# Intan_Headstage.net
KiCad netlist of a schematic drawn in EAGLE
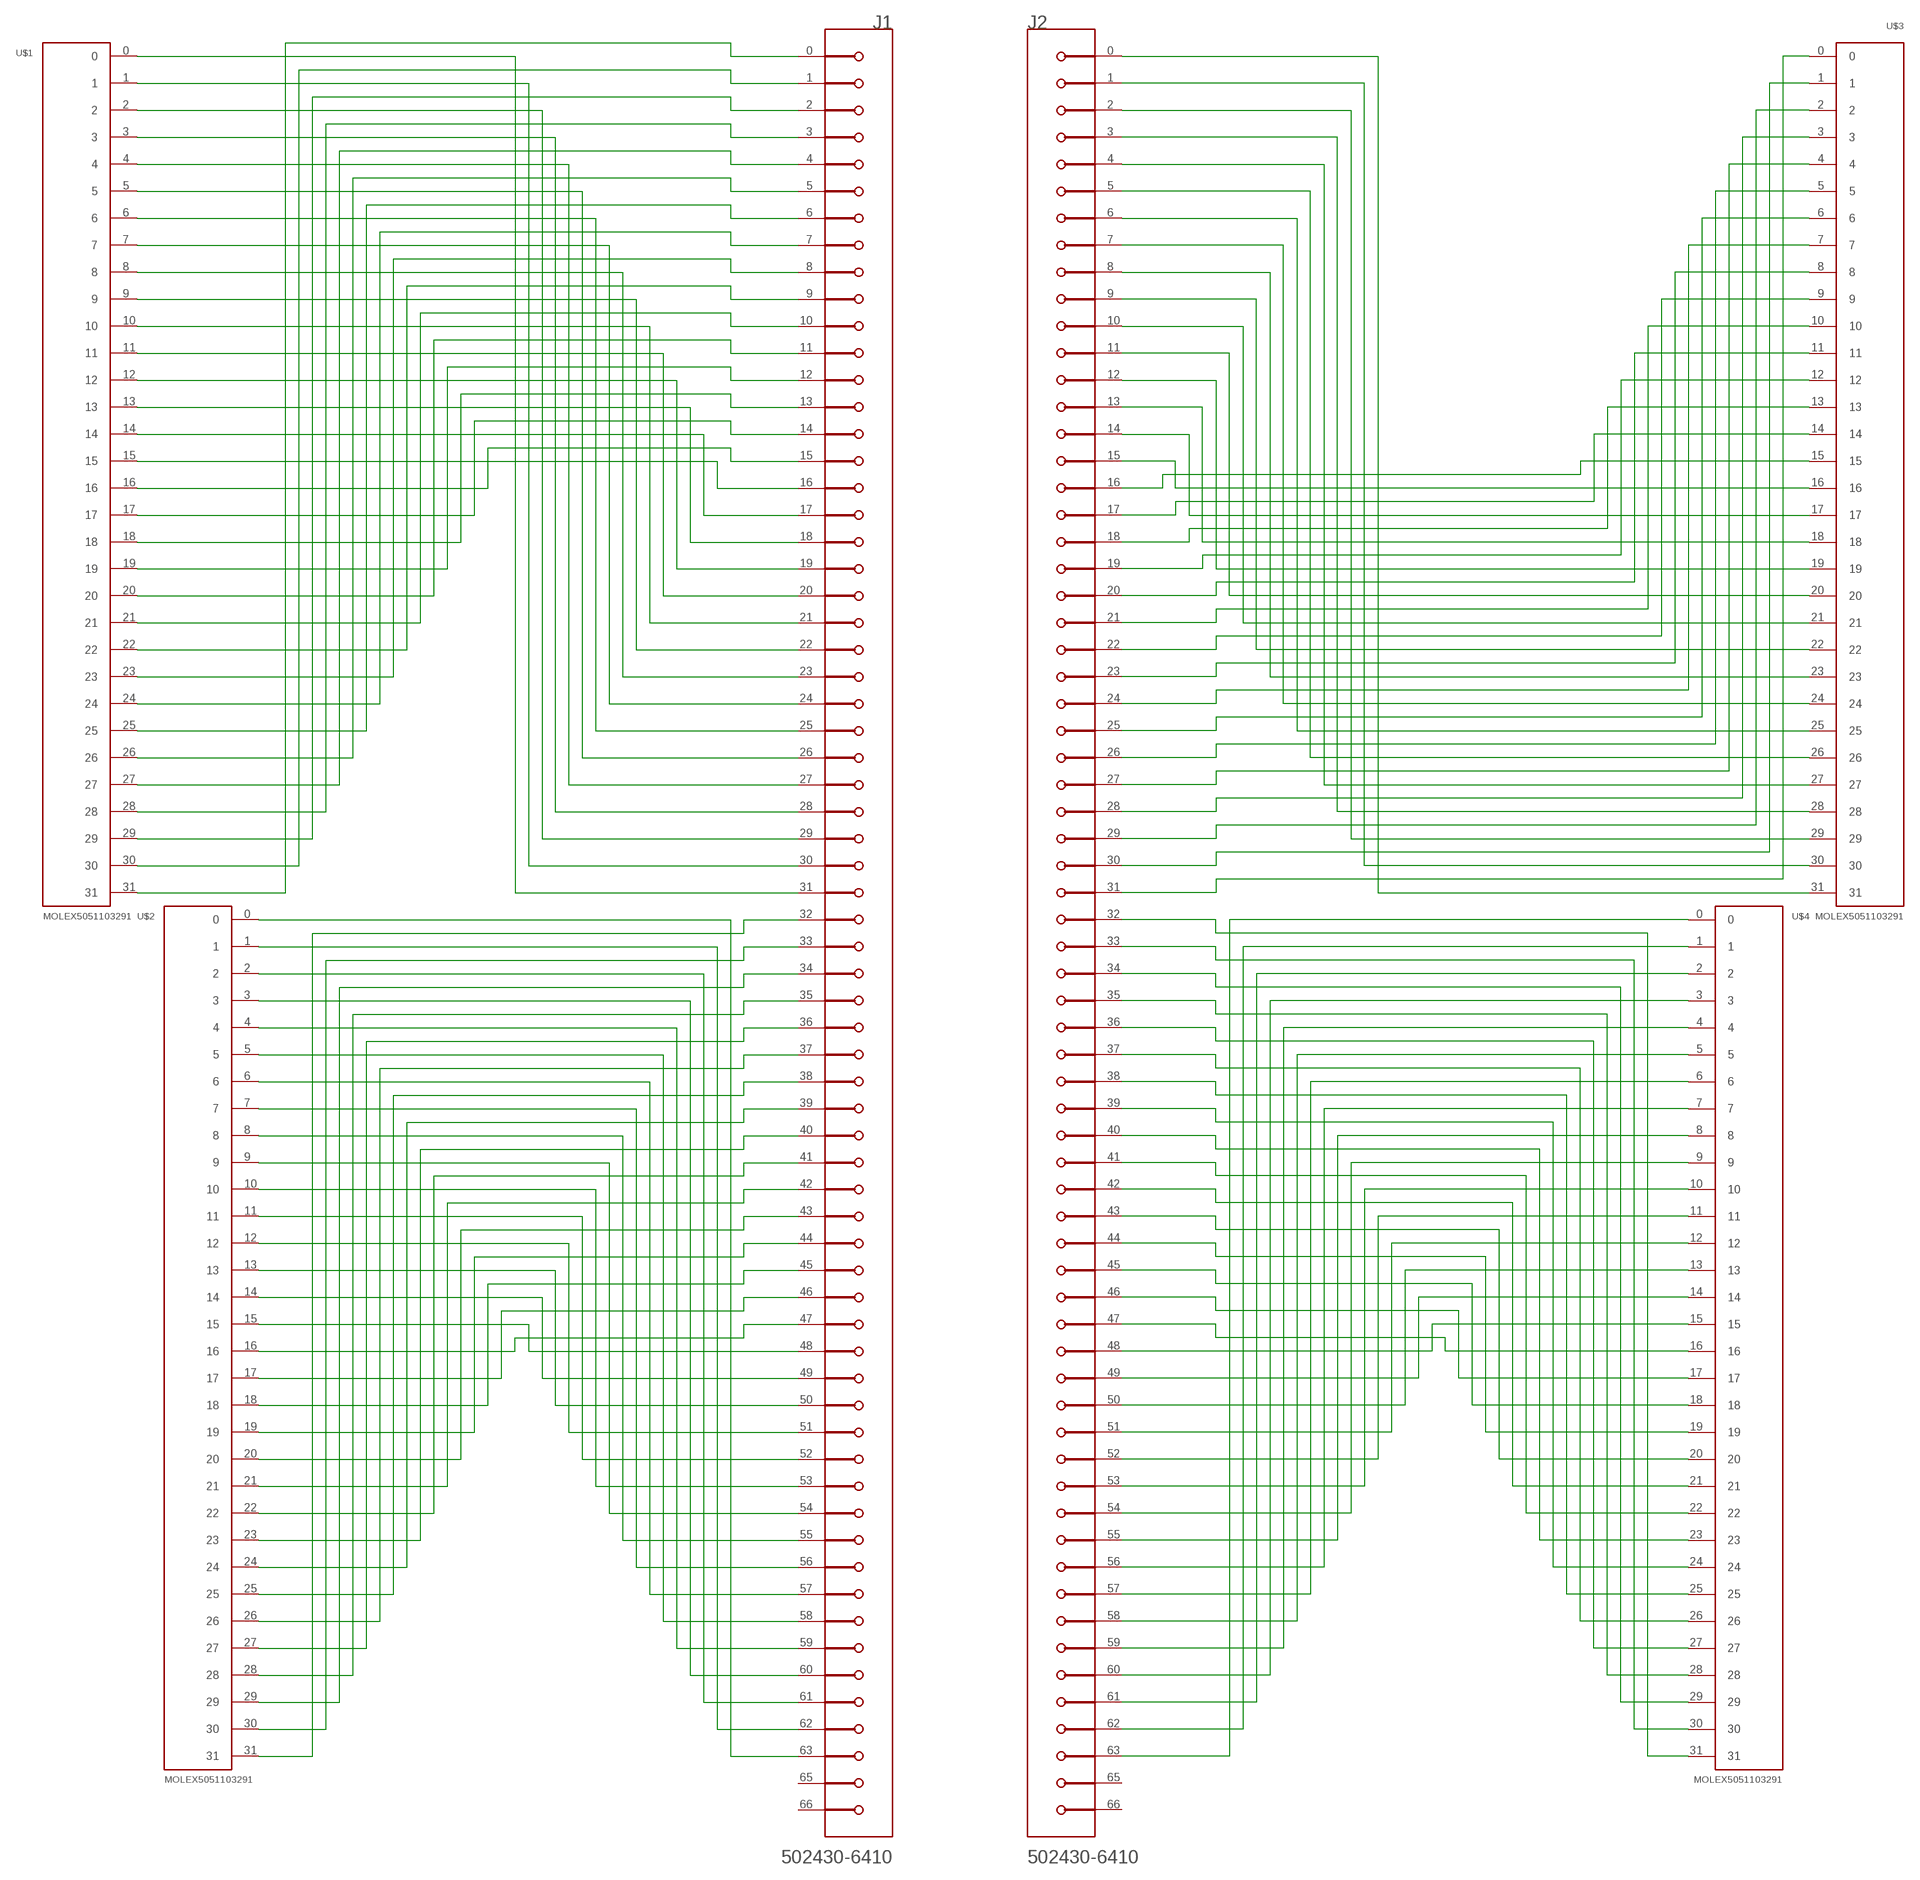
[diagram p0: schematic, sheet 1]

(export (version "E")
  (design (tool "Eeschema 10.0.6"))
  (components
    (comp (ref "J1")
      (value "MOLEX_502430-6410MOLEX_502430-6410_0_0")
      (footprint "eagle-import:MOLEX_502430-6410_0")
      (fields
        (field (name "DIGIKEY_PART_NUMBER") "WM24084TR-ND")
        (field (name "MF") "Molex")
        (field (name "MOUSER_PART_NUMBER") "538-502430-6410")
      )
      (libsource (lib "eagle-import") (part "MOLEX_502430-6410MOLEX_502430-6410_0_0"))
    )
    (comp (ref "J2")
      (value "MOLEX_502430-6410MOLEX_502430-6410_0_0")
      (footprint "eagle-import:MOLEX_502430-6410_0")
      (fields
        (field (name "DIGIKEY_PART_NUMBER") "WM24084TR-ND")
        (field (name "MF") "Molex")
        (field (name "MOUSER_PART_NUMBER") "538-502430-6410")
      )
      (libsource (lib "eagle-import") (part "MOLEX_502430-6410MOLEX_502430-6410_0_0"))
    )
    (comp (ref "U$1")
      (value "MOLEX5051103291")
      (footprint "eagle-import:MOLEX5051103291")
      (libsource (lib "eagle-import") (part "MOLEX5051103291"))
    )
    (comp (ref "U$2")
      (value "MOLEX5051103291")
      (footprint "eagle-import:MOLEX5051103291")
      (libsource (lib "eagle-import") (part "MOLEX5051103291"))
    )
    (comp (ref "U$3")
      (value "MOLEX5051103291")
      (footprint "eagle-import:MOLEX5051103291")
      (libsource (lib "eagle-import") (part "MOLEX5051103291"))
    )
    (comp (ref "U$4")
      (value "MOLEX5051103291")
      (footprint "eagle-import:MOLEX5051103291")
      (libsource (lib "eagle-import") (part "MOLEX5051103291"))
    )
  )
  (nets
    (net (code "1") (name "Net-(J1-1)") (class "Default")
      (node (ref "J1") (pin "0") (pinfunction "1_0") (pintype "bidirectional"))
      (node (ref "U$1") (pin "31") (pinfunction "31_31") (pintype "bidirectional"))
    )
    (net (code "2") (name "Net-(J1-2)") (class "Default")
      (node (ref "J1") (pin "1") (pinfunction "2_1") (pintype "bidirectional"))
      (node (ref "U$1") (pin "30") (pinfunction "30_30") (pintype "bidirectional"))
    )
    (net (code "3") (name "Net-(J1-3)") (class "Default")
      (node (ref "J1") (pin "2") (pinfunction "3_2") (pintype "bidirectional"))
      (node (ref "U$1") (pin "29") (pinfunction "29_29") (pintype "bidirectional"))
    )
    (net (code "4") (name "Net-(J1-4)") (class "Default")
      (node (ref "J1") (pin "3") (pinfunction "4_3") (pintype "bidirectional"))
      (node (ref "U$1") (pin "28") (pinfunction "28_28") (pintype "bidirectional"))
    )
    (net (code "5") (name "Net-(J1-5)") (class "Default")
      (node (ref "J1") (pin "4") (pinfunction "5_4") (pintype "bidirectional"))
      (node (ref "U$1") (pin "27") (pinfunction "27_27") (pintype "bidirectional"))
    )
    (net (code "6") (name "Net-(J1-6)") (class "Default")
      (node (ref "J1") (pin "5") (pinfunction "6_5") (pintype "bidirectional"))
      (node (ref "U$1") (pin "26") (pinfunction "26_26") (pintype "bidirectional"))
    )
    (net (code "7") (name "Net-(J1-7)") (class "Default")
      (node (ref "J1") (pin "6") (pinfunction "7_6") (pintype "bidirectional"))
      (node (ref "U$1") (pin "25") (pinfunction "25_25") (pintype "bidirectional"))
    )
    (net (code "8") (name "Net-(J1-8)") (class "Default")
      (node (ref "J1") (pin "7") (pinfunction "8_7") (pintype "bidirectional"))
      (node (ref "U$1") (pin "24") (pinfunction "24_24") (pintype "bidirectional"))
    )
    (net (code "9") (name "Net-(J1-9)") (class "Default")
      (node (ref "J1") (pin "8") (pinfunction "9_8") (pintype "bidirectional"))
      (node (ref "U$1") (pin "23") (pinfunction "23_23") (pintype "bidirectional"))
    )
    (net (code "10") (name "Net-(J1-10)") (class "Default")
      (node (ref "J1") (pin "9") (pinfunction "10_9") (pintype "bidirectional"))
      (node (ref "U$1") (pin "22") (pinfunction "22_22") (pintype "bidirectional"))
    )
    (net (code "11") (name "Net-(J1-11)") (class "Default")
      (node (ref "J1") (pin "10") (pinfunction "11_10") (pintype "bidirectional"))
      (node (ref "U$1") (pin "21") (pinfunction "21_21") (pintype "bidirectional"))
    )
    (net (code "12") (name "Net-(J1-12)") (class "Default")
      (node (ref "J1") (pin "11") (pinfunction "12_11") (pintype "bidirectional"))
      (node (ref "U$1") (pin "20") (pinfunction "20_20") (pintype "bidirectional"))
    )
    (net (code "13") (name "Net-(J1-13)") (class "Default")
      (node (ref "J1") (pin "12") (pinfunction "13_12") (pintype "bidirectional"))
      (node (ref "U$1") (pin "19") (pinfunction "19_19") (pintype "bidirectional"))
    )
    (net (code "14") (name "Net-(J1-14)") (class "Default")
      (node (ref "J1") (pin "13") (pinfunction "14_13") (pintype "bidirectional"))
      (node (ref "U$1") (pin "18") (pinfunction "18_18") (pintype "bidirectional"))
    )
    (net (code "15") (name "Net-(J1-15)") (class "Default")
      (node (ref "J1") (pin "14") (pinfunction "15_14") (pintype "bidirectional"))
      (node (ref "U$1") (pin "17") (pinfunction "17_17") (pintype "bidirectional"))
    )
    (net (code "16") (name "Net-(J1-16)") (class "Default")
      (node (ref "J1") (pin "15") (pinfunction "16_15") (pintype "bidirectional"))
      (node (ref "U$1") (pin "16") (pinfunction "16_16") (pintype "bidirectional"))
    )
    (net (code "17") (name "Net-(J1-17)") (class "Default")
      (node (ref "J1") (pin "16") (pinfunction "17_16") (pintype "bidirectional"))
      (node (ref "U$1") (pin "15") (pinfunction "15_15") (pintype "bidirectional"))
    )
    (net (code "18") (name "Net-(J1-18)") (class "Default")
      (node (ref "J1") (pin "17") (pinfunction "18_17") (pintype "bidirectional"))
      (node (ref "U$1") (pin "14") (pinfunction "14_14") (pintype "bidirectional"))
    )
    (net (code "19") (name "Net-(J1-19)") (class "Default")
      (node (ref "J1") (pin "18") (pinfunction "19_18") (pintype "bidirectional"))
      (node (ref "U$1") (pin "13") (pinfunction "13_13") (pintype "bidirectional"))
    )
    (net (code "20") (name "Net-(J1-20)") (class "Default")
      (node (ref "J1") (pin "19") (pinfunction "20_19") (pintype "bidirectional"))
      (node (ref "U$1") (pin "12") (pinfunction "12_12") (pintype "bidirectional"))
    )
    (net (code "21") (name "Net-(J1-21)") (class "Default")
      (node (ref "J1") (pin "20") (pinfunction "21_20") (pintype "bidirectional"))
      (node (ref "U$1") (pin "11") (pinfunction "11_11") (pintype "bidirectional"))
    )
    (net (code "22") (name "Net-(J1-22)") (class "Default")
      (node (ref "J1") (pin "21") (pinfunction "22_21") (pintype "bidirectional"))
      (node (ref "U$1") (pin "10") (pinfunction "10_10") (pintype "bidirectional"))
    )
    (net (code "23") (name "Net-(J1-23)") (class "Default")
      (node (ref "J1") (pin "22") (pinfunction "23_22") (pintype "bidirectional"))
      (node (ref "U$1") (pin "9") (pinfunction "9_9") (pintype "bidirectional"))
    )
    (net (code "24") (name "Net-(J1-24)") (class "Default")
      (node (ref "J1") (pin "23") (pinfunction "24_23") (pintype "bidirectional"))
      (node (ref "U$1") (pin "8") (pinfunction "8_8") (pintype "bidirectional"))
    )
    (net (code "25") (name "Net-(J1-25)") (class "Default")
      (node (ref "J1") (pin "24") (pinfunction "25_24") (pintype "bidirectional"))
      (node (ref "U$1") (pin "7") (pinfunction "7_7") (pintype "bidirectional"))
    )
    (net (code "26") (name "Net-(J1-26)") (class "Default")
      (node (ref "J1") (pin "25") (pinfunction "26_25") (pintype "bidirectional"))
      (node (ref "U$1") (pin "6") (pinfunction "6_6") (pintype "bidirectional"))
    )
    (net (code "27") (name "Net-(J1-27)") (class "Default")
      (node (ref "J1") (pin "26") (pinfunction "27_26") (pintype "bidirectional"))
      (node (ref "U$1") (pin "5") (pinfunction "5_5") (pintype "bidirectional"))
    )
    (net (code "28") (name "Net-(J1-28)") (class "Default")
      (node (ref "J1") (pin "27") (pinfunction "28_27") (pintype "bidirectional"))
      (node (ref "U$1") (pin "4") (pinfunction "4_4") (pintype "bidirectional"))
    )
    (net (code "29") (name "Net-(J1-29)") (class "Default")
      (node (ref "J1") (pin "28") (pinfunction "29_28") (pintype "bidirectional"))
      (node (ref "U$1") (pin "3") (pinfunction "3_3") (pintype "bidirectional"))
    )
    (net (code "30") (name "Net-(J1-30)") (class "Default")
      (node (ref "J1") (pin "29") (pinfunction "30_29") (pintype "bidirectional"))
      (node (ref "U$1") (pin "2") (pinfunction "2_2") (pintype "bidirectional"))
    )
    (net (code "31") (name "Net-(J1-31)") (class "Default")
      (node (ref "J1") (pin "30") (pinfunction "31_30") (pintype "bidirectional"))
      (node (ref "U$1") (pin "1") (pinfunction "1_1") (pintype "bidirectional"))
    )
    (net (code "32") (name "Net-(J1-32)") (class "Default")
      (node (ref "J1") (pin "31") (pinfunction "32_31") (pintype "bidirectional"))
      (node (ref "U$1") (pin "0") (pinfunction "0_0") (pintype "bidirectional"))
    )
    (net (code "33") (name "Net-(J1-33)") (class "Default")
      (node (ref "J1") (pin "32") (pinfunction "33_32") (pintype "bidirectional"))
      (node (ref "U$2") (pin "31") (pinfunction "31_31") (pintype "bidirectional"))
    )
    (net (code "34") (name "Net-(J1-34)") (class "Default")
      (node (ref "J1") (pin "33") (pinfunction "34_33") (pintype "bidirectional"))
      (node (ref "U$2") (pin "30") (pinfunction "30_30") (pintype "bidirectional"))
    )
    (net (code "35") (name "Net-(J1-35)") (class "Default")
      (node (ref "J1") (pin "34") (pinfunction "35_34") (pintype "bidirectional"))
      (node (ref "U$2") (pin "29") (pinfunction "29_29") (pintype "bidirectional"))
    )
    (net (code "36") (name "Net-(J1-36)") (class "Default")
      (node (ref "J1") (pin "35") (pinfunction "36_35") (pintype "bidirectional"))
      (node (ref "U$2") (pin "28") (pinfunction "28_28") (pintype "bidirectional"))
    )
    (net (code "37") (name "Net-(J1-37)") (class "Default")
      (node (ref "J1") (pin "36") (pinfunction "37_36") (pintype "bidirectional"))
      (node (ref "U$2") (pin "27") (pinfunction "27_27") (pintype "bidirectional"))
    )
    (net (code "38") (name "Net-(J1-38)") (class "Default")
      (node (ref "J1") (pin "37") (pinfunction "38_37") (pintype "bidirectional"))
      (node (ref "U$2") (pin "26") (pinfunction "26_26") (pintype "bidirectional"))
    )
    (net (code "39") (name "Net-(J1-39)") (class "Default")
      (node (ref "J1") (pin "38") (pinfunction "39_38") (pintype "bidirectional"))
      (node (ref "U$2") (pin "25") (pinfunction "25_25") (pintype "bidirectional"))
    )
    (net (code "40") (name "Net-(J1-40)") (class "Default")
      (node (ref "J1") (pin "39") (pinfunction "40_39") (pintype "bidirectional"))
      (node (ref "U$2") (pin "24") (pinfunction "24_24") (pintype "bidirectional"))
    )
    (net (code "41") (name "Net-(J1-41)") (class "Default")
      (node (ref "J1") (pin "40") (pinfunction "41_40") (pintype "bidirectional"))
      (node (ref "U$2") (pin "23") (pinfunction "23_23") (pintype "bidirectional"))
    )
    (net (code "42") (name "Net-(J1-42)") (class "Default")
      (node (ref "J1") (pin "41") (pinfunction "42_41") (pintype "bidirectional"))
      (node (ref "U$2") (pin "22") (pinfunction "22_22") (pintype "bidirectional"))
    )
    (net (code "43") (name "Net-(J1-43)") (class "Default")
      (node (ref "J1") (pin "42") (pinfunction "43_42") (pintype "bidirectional"))
      (node (ref "U$2") (pin "21") (pinfunction "21_21") (pintype "bidirectional"))
    )
    (net (code "44") (name "Net-(J1-44)") (class "Default")
      (node (ref "J1") (pin "43") (pinfunction "44_43") (pintype "bidirectional"))
      (node (ref "U$2") (pin "20") (pinfunction "20_20") (pintype "bidirectional"))
    )
    (net (code "45") (name "Net-(J1-45)") (class "Default")
      (node (ref "J1") (pin "44") (pinfunction "45_44") (pintype "bidirectional"))
      (node (ref "U$2") (pin "19") (pinfunction "19_19") (pintype "bidirectional"))
    )
    (net (code "46") (name "Net-(J1-46)") (class "Default")
      (node (ref "J1") (pin "45") (pinfunction "46_45") (pintype "bidirectional"))
      (node (ref "U$2") (pin "18") (pinfunction "18_18") (pintype "bidirectional"))
    )
    (net (code "47") (name "Net-(J1-47)") (class "Default")
      (node (ref "J1") (pin "46") (pinfunction "47_46") (pintype "bidirectional"))
      (node (ref "U$2") (pin "17") (pinfunction "17_17") (pintype "bidirectional"))
    )
    (net (code "48") (name "Net-(J1-48)") (class "Default")
      (node (ref "J1") (pin "47") (pinfunction "48_47") (pintype "bidirectional"))
      (node (ref "U$2") (pin "16") (pinfunction "16_16") (pintype "bidirectional"))
    )
    (net (code "49") (name "Net-(J1-49)") (class "Default")
      (node (ref "J1") (pin "48") (pinfunction "49_48") (pintype "bidirectional"))
      (node (ref "U$2") (pin "15") (pinfunction "15_15") (pintype "bidirectional"))
    )
    (net (code "50") (name "Net-(J1-50)") (class "Default")
      (node (ref "J1") (pin "49") (pinfunction "50_49") (pintype "bidirectional"))
      (node (ref "U$2") (pin "14") (pinfunction "14_14") (pintype "bidirectional"))
    )
    (net (code "51") (name "Net-(J1-51)") (class "Default")
      (node (ref "J1") (pin "50") (pinfunction "51_50") (pintype "bidirectional"))
      (node (ref "U$2") (pin "13") (pinfunction "13_13") (pintype "bidirectional"))
    )
    (net (code "52") (name "Net-(J1-52)") (class "Default")
      (node (ref "J1") (pin "51") (pinfunction "52_51") (pintype "bidirectional"))
      (node (ref "U$2") (pin "12") (pinfunction "12_12") (pintype "bidirectional"))
    )
    (net (code "53") (name "Net-(J1-53)") (class "Default")
      (node (ref "J1") (pin "52") (pinfunction "53_52") (pintype "bidirectional"))
      (node (ref "U$2") (pin "11") (pinfunction "11_11") (pintype "bidirectional"))
    )
    (net (code "54") (name "Net-(J1-54)") (class "Default")
      (node (ref "J1") (pin "53") (pinfunction "54_53") (pintype "bidirectional"))
      (node (ref "U$2") (pin "10") (pinfunction "10_10") (pintype "bidirectional"))
    )
    (net (code "55") (name "Net-(J1-55)") (class "Default")
      (node (ref "J1") (pin "54") (pinfunction "55_54") (pintype "bidirectional"))
      (node (ref "U$2") (pin "9") (pinfunction "9_9") (pintype "bidirectional"))
    )
    (net (code "56") (name "Net-(J1-56)") (class "Default")
      (node (ref "J1") (pin "55") (pinfunction "56_55") (pintype "bidirectional"))
      (node (ref "U$2") (pin "8") (pinfunction "8_8") (pintype "bidirectional"))
    )
    (net (code "57") (name "Net-(J1-57)") (class "Default")
      (node (ref "J1") (pin "56") (pinfunction "57_56") (pintype "bidirectional"))
      (node (ref "U$2") (pin "7") (pinfunction "7_7") (pintype "bidirectional"))
    )
    (net (code "58") (name "Net-(J1-58)") (class "Default")
      (node (ref "J1") (pin "57") (pinfunction "58_57") (pintype "bidirectional"))
      (node (ref "U$2") (pin "6") (pinfunction "6_6") (pintype "bidirectional"))
    )
    (net (code "59") (name "Net-(J1-59)") (class "Default")
      (node (ref "J1") (pin "58") (pinfunction "59_58") (pintype "bidirectional"))
      (node (ref "U$2") (pin "5") (pinfunction "5_5") (pintype "bidirectional"))
    )
    (net (code "60") (name "Net-(J1-60)") (class "Default")
      (node (ref "J1") (pin "59") (pinfunction "60_59") (pintype "bidirectional"))
      (node (ref "U$2") (pin "4") (pinfunction "4_4") (pintype "bidirectional"))
    )
    (net (code "61") (name "Net-(J1-61)") (class "Default")
      (node (ref "J1") (pin "60") (pinfunction "61_60") (pintype "bidirectional"))
      (node (ref "U$2") (pin "3") (pinfunction "3_3") (pintype "bidirectional"))
    )
    (net (code "62") (name "Net-(J1-62)") (class "Default")
      (node (ref "J1") (pin "61") (pinfunction "62_61") (pintype "bidirectional"))
      (node (ref "U$2") (pin "2") (pinfunction "2_2") (pintype "bidirectional"))
    )
    (net (code "63") (name "Net-(J1-63)") (class "Default")
      (node (ref "J1") (pin "62") (pinfunction "63_62") (pintype "bidirectional"))
      (node (ref "U$2") (pin "1") (pinfunction "1_1") (pintype "bidirectional"))
    )
    (net (code "64") (name "Net-(J1-64)") (class "Default")
      (node (ref "J1") (pin "63") (pinfunction "64_63") (pintype "bidirectional"))
      (node (ref "U$2") (pin "0") (pinfunction "0_0") (pintype "bidirectional"))
    )
    (net (code "65") (name "Net-(J2-1)") (class "Default")
      (node (ref "J2") (pin "0") (pinfunction "1_0") (pintype "bidirectional"))
      (node (ref "U$3") (pin "31") (pinfunction "31_31") (pintype "bidirectional"))
    )
    (net (code "66") (name "Net-(J2-2)") (class "Default")
      (node (ref "J2") (pin "1") (pinfunction "2_1") (pintype "bidirectional"))
      (node (ref "U$3") (pin "30") (pinfunction "30_30") (pintype "bidirectional"))
    )
    (net (code "67") (name "Net-(J2-3)") (class "Default")
      (node (ref "J2") (pin "2") (pinfunction "3_2") (pintype "bidirectional"))
      (node (ref "U$3") (pin "29") (pinfunction "29_29") (pintype "bidirectional"))
    )
    (net (code "68") (name "Net-(J2-4)") (class "Default")
      (node (ref "J2") (pin "3") (pinfunction "4_3") (pintype "bidirectional"))
      (node (ref "U$3") (pin "28") (pinfunction "28_28") (pintype "bidirectional"))
    )
    (net (code "69") (name "Net-(J2-5)") (class "Default")
      (node (ref "J2") (pin "4") (pinfunction "5_4") (pintype "bidirectional"))
      (node (ref "U$3") (pin "27") (pinfunction "27_27") (pintype "bidirectional"))
    )
    (net (code "70") (name "Net-(J2-6)") (class "Default")
      (node (ref "J2") (pin "5") (pinfunction "6_5") (pintype "bidirectional"))
      (node (ref "U$3") (pin "26") (pinfunction "26_26") (pintype "bidirectional"))
    )
    (net (code "71") (name "Net-(J2-7)") (class "Default")
      (node (ref "J2") (pin "6") (pinfunction "7_6") (pintype "bidirectional"))
      (node (ref "U$3") (pin "25") (pinfunction "25_25") (pintype "bidirectional"))
    )
    (net (code "72") (name "Net-(J2-8)") (class "Default")
      (node (ref "J2") (pin "7") (pinfunction "8_7") (pintype "bidirectional"))
      (node (ref "U$3") (pin "24") (pinfunction "24_24") (pintype "bidirectional"))
    )
    (net (code "73") (name "Net-(J2-9)") (class "Default")
      (node (ref "J2") (pin "8") (pinfunction "9_8") (pintype "bidirectional"))
      (node (ref "U$3") (pin "23") (pinfunction "23_23") (pintype "bidirectional"))
    )
    (net (code "74") (name "Net-(J2-10)") (class "Default")
      (node (ref "J2") (pin "9") (pinfunction "10_9") (pintype "bidirectional"))
      (node (ref "U$3") (pin "22") (pinfunction "22_22") (pintype "bidirectional"))
    )
    (net (code "75") (name "Net-(J2-11)") (class "Default")
      (node (ref "J2") (pin "10") (pinfunction "11_10") (pintype "bidirectional"))
      (node (ref "U$3") (pin "21") (pinfunction "21_21") (pintype "bidirectional"))
    )
    (net (code "76") (name "Net-(J2-12)") (class "Default")
      (node (ref "J2") (pin "11") (pinfunction "12_11") (pintype "bidirectional"))
      (node (ref "U$3") (pin "20") (pinfunction "20_20") (pintype "bidirectional"))
    )
    (net (code "77") (name "Net-(J2-13)") (class "Default")
      (node (ref "J2") (pin "12") (pinfunction "13_12") (pintype "bidirectional"))
      (node (ref "U$3") (pin "19") (pinfunction "19_19") (pintype "bidirectional"))
    )
    (net (code "78") (name "Net-(J2-14)") (class "Default")
      (node (ref "J2") (pin "13") (pinfunction "14_13") (pintype "bidirectional"))
      (node (ref "U$3") (pin "18") (pinfunction "18_18") (pintype "bidirectional"))
    )
    (net (code "79") (name "Net-(J2-15)") (class "Default")
      (node (ref "J2") (pin "14") (pinfunction "15_14") (pintype "bidirectional"))
      (node (ref "U$3") (pin "17") (pinfunction "17_17") (pintype "bidirectional"))
    )
    (net (code "80") (name "Net-(J2-16)") (class "Default")
      (node (ref "J2") (pin "15") (pinfunction "16_15") (pintype "bidirectional"))
      (node (ref "U$3") (pin "16") (pinfunction "16_16") (pintype "bidirectional"))
    )
    (net (code "81") (name "Net-(J2-17)") (class "Default")
      (node (ref "J2") (pin "16") (pinfunction "17_16") (pintype "bidirectional"))
      (node (ref "U$3") (pin "15") (pinfunction "15_15") (pintype "bidirectional"))
    )
    (net (code "82") (name "Net-(J2-18)") (class "Default")
      (node (ref "J2") (pin "17") (pinfunction "18_17") (pintype "bidirectional"))
      (node (ref "U$3") (pin "14") (pinfunction "14_14") (pintype "bidirectional"))
    )
    (net (code "83") (name "Net-(J2-19)") (class "Default")
      (node (ref "J2") (pin "18") (pinfunction "19_18") (pintype "bidirectional"))
      (node (ref "U$3") (pin "13") (pinfunction "13_13") (pintype "bidirectional"))
    )
    (net (code "84") (name "Net-(J2-20)") (class "Default")
      (node (ref "J2") (pin "19") (pinfunction "20_19") (pintype "bidirectional"))
      (node (ref "U$3") (pin "12") (pinfunction "12_12") (pintype "bidirectional"))
    )
    (net (code "85") (name "Net-(J2-21)") (class "Default")
      (node (ref "J2") (pin "20") (pinfunction "21_20") (pintype "bidirectional"))
      (node (ref "U$3") (pin "11") (pinfunction "11_11") (pintype "bidirectional"))
    )
    (net (code "86") (name "Net-(J2-22)") (class "Default")
      (node (ref "J2") (pin "21") (pinfunction "22_21") (pintype "bidirectional"))
      (node (ref "U$3") (pin "10") (pinfunction "10_10") (pintype "bidirectional"))
    )
    (net (code "87") (name "Net-(J2-23)") (class "Default")
      (node (ref "J2") (pin "22") (pinfunction "23_22") (pintype "bidirectional"))
      (node (ref "U$3") (pin "9") (pinfunction "9_9") (pintype "bidirectional"))
    )
    (net (code "88") (name "Net-(J2-24)") (class "Default")
      (node (ref "J2") (pin "23") (pinfunction "24_23") (pintype "bidirectional"))
      (node (ref "U$3") (pin "8") (pinfunction "8_8") (pintype "bidirectional"))
    )
    (net (code "89") (name "Net-(J2-25)") (class "Default")
      (node (ref "J2") (pin "24") (pinfunction "25_24") (pintype "bidirectional"))
      (node (ref "U$3") (pin "7") (pinfunction "7_7") (pintype "bidirectional"))
    )
    (net (code "90") (name "Net-(J2-26)") (class "Default")
      (node (ref "J2") (pin "25") (pinfunction "26_25") (pintype "bidirectional"))
      (node (ref "U$3") (pin "6") (pinfunction "6_6") (pintype "bidirectional"))
    )
    (net (code "91") (name "Net-(J2-27)") (class "Default")
      (node (ref "J2") (pin "26") (pinfunction "27_26") (pintype "bidirectional"))
      (node (ref "U$3") (pin "5") (pinfunction "5_5") (pintype "bidirectional"))
    )
    (net (code "92") (name "Net-(J2-28)") (class "Default")
      (node (ref "J2") (pin "27") (pinfunction "28_27") (pintype "bidirectional"))
      (node (ref "U$3") (pin "4") (pinfunction "4_4") (pintype "bidirectional"))
    )
    (net (code "93") (name "Net-(J2-29)") (class "Default")
      (node (ref "J2") (pin "28") (pinfunction "29_28") (pintype "bidirectional"))
      (node (ref "U$3") (pin "3") (pinfunction "3_3") (pintype "bidirectional"))
    )
    (net (code "94") (name "Net-(J2-30)") (class "Default")
      (node (ref "J2") (pin "29") (pinfunction "30_29") (pintype "bidirectional"))
      (node (ref "U$3") (pin "2") (pinfunction "2_2") (pintype "bidirectional"))
    )
    (net (code "95") (name "Net-(J2-31)") (class "Default")
      (node (ref "J2") (pin "30") (pinfunction "31_30") (pintype "bidirectional"))
      (node (ref "U$3") (pin "1") (pinfunction "1_1") (pintype "bidirectional"))
    )
    (net (code "96") (name "Net-(J2-32)") (class "Default")
      (node (ref "J2") (pin "31") (pinfunction "32_31") (pintype "bidirectional"))
      (node (ref "U$3") (pin "0") (pinfunction "0_0") (pintype "bidirectional"))
    )
    (net (code "97") (name "Net-(J2-33)") (class "Default")
      (node (ref "J2") (pin "32") (pinfunction "33_32") (pintype "bidirectional"))
      (node (ref "U$4") (pin "31") (pinfunction "31_31") (pintype "bidirectional"))
    )
    (net (code "98") (name "Net-(J2-34)") (class "Default")
      (node (ref "J2") (pin "33") (pinfunction "34_33") (pintype "bidirectional"))
      (node (ref "U$4") (pin "30") (pinfunction "30_30") (pintype "bidirectional"))
    )
    (net (code "99") (name "Net-(J2-35)") (class "Default")
      (node (ref "J2") (pin "34") (pinfunction "35_34") (pintype "bidirectional"))
      (node (ref "U$4") (pin "29") (pinfunction "29_29") (pintype "bidirectional"))
    )
    (net (code "100") (name "Net-(J2-36)") (class "Default")
      (node (ref "J2") (pin "35") (pinfunction "36_35") (pintype "bidirectional"))
      (node (ref "U$4") (pin "28") (pinfunction "28_28") (pintype "bidirectional"))
    )
    (net (code "101") (name "Net-(J2-37)") (class "Default")
      (node (ref "J2") (pin "36") (pinfunction "37_36") (pintype "bidirectional"))
      (node (ref "U$4") (pin "27") (pinfunction "27_27") (pintype "bidirectional"))
    )
    (net (code "102") (name "Net-(J2-38)") (class "Default")
      (node (ref "J2") (pin "37") (pinfunction "38_37") (pintype "bidirectional"))
      (node (ref "U$4") (pin "26") (pinfunction "26_26") (pintype "bidirectional"))
    )
    (net (code "103") (name "Net-(J2-39)") (class "Default")
      (node (ref "J2") (pin "38") (pinfunction "39_38") (pintype "bidirectional"))
      (node (ref "U$4") (pin "25") (pinfunction "25_25") (pintype "bidirectional"))
    )
    (net (code "104") (name "Net-(J2-40)") (class "Default")
      (node (ref "J2") (pin "39") (pinfunction "40_39") (pintype "bidirectional"))
      (node (ref "U$4") (pin "24") (pinfunction "24_24") (pintype "bidirectional"))
    )
    (net (code "105") (name "Net-(J2-41)") (class "Default")
      (node (ref "J2") (pin "40") (pinfunction "41_40") (pintype "bidirectional"))
      (node (ref "U$4") (pin "23") (pinfunction "23_23") (pintype "bidirectional"))
    )
    (net (code "106") (name "Net-(J2-42)") (class "Default")
      (node (ref "J2") (pin "41") (pinfunction "42_41") (pintype "bidirectional"))
      (node (ref "U$4") (pin "22") (pinfunction "22_22") (pintype "bidirectional"))
    )
    (net (code "107") (name "Net-(J2-43)") (class "Default")
      (node (ref "J2") (pin "42") (pinfunction "43_42") (pintype "bidirectional"))
      (node (ref "U$4") (pin "21") (pinfunction "21_21") (pintype "bidirectional"))
    )
    (net (code "108") (name "Net-(J2-44)") (class "Default")
      (node (ref "J2") (pin "43") (pinfunction "44_43") (pintype "bidirectional"))
      (node (ref "U$4") (pin "20") (pinfunction "20_20") (pintype "bidirectional"))
    )
    (net (code "109") (name "Net-(J2-45)") (class "Default")
      (node (ref "J2") (pin "44") (pinfunction "45_44") (pintype "bidirectional"))
      (node (ref "U$4") (pin "19") (pinfunction "19_19") (pintype "bidirectional"))
    )
    (net (code "110") (name "Net-(J2-46)") (class "Default")
      (node (ref "J2") (pin "45") (pinfunction "46_45") (pintype "bidirectional"))
      (node (ref "U$4") (pin "18") (pinfunction "18_18") (pintype "bidirectional"))
    )
    (net (code "111") (name "Net-(J2-47)") (class "Default")
      (node (ref "J2") (pin "46") (pinfunction "47_46") (pintype "bidirectional"))
      (node (ref "U$4") (pin "17") (pinfunction "17_17") (pintype "bidirectional"))
    )
    (net (code "112") (name "Net-(J2-48)") (class "Default")
      (node (ref "J2") (pin "47") (pinfunction "48_47") (pintype "bidirectional"))
      (node (ref "U$4") (pin "16") (pinfunction "16_16") (pintype "bidirectional"))
    )
    (net (code "113") (name "Net-(J2-49)") (class "Default")
      (node (ref "J2") (pin "48") (pinfunction "49_48") (pintype "bidirectional"))
      (node (ref "U$4") (pin "15") (pinfunction "15_15") (pintype "bidirectional"))
    )
    (net (code "114") (name "Net-(J2-50)") (class "Default")
      (node (ref "J2") (pin "49") (pinfunction "50_49") (pintype "bidirectional"))
      (node (ref "U$4") (pin "14") (pinfunction "14_14") (pintype "bidirectional"))
    )
    (net (code "115") (name "Net-(J2-51)") (class "Default")
      (node (ref "J2") (pin "50") (pinfunction "51_50") (pintype "bidirectional"))
      (node (ref "U$4") (pin "13") (pinfunction "13_13") (pintype "bidirectional"))
    )
    (net (code "116") (name "Net-(J2-52)") (class "Default")
      (node (ref "J2") (pin "51") (pinfunction "52_51") (pintype "bidirectional"))
      (node (ref "U$4") (pin "12") (pinfunction "12_12") (pintype "bidirectional"))
    )
    (net (code "117") (name "Net-(J2-53)") (class "Default")
      (node (ref "J2") (pin "52") (pinfunction "53_52") (pintype "bidirectional"))
      (node (ref "U$4") (pin "11") (pinfunction "11_11") (pintype "bidirectional"))
    )
    (net (code "118") (name "Net-(J2-54)") (class "Default")
      (node (ref "J2") (pin "53") (pinfunction "54_53") (pintype "bidirectional"))
      (node (ref "U$4") (pin "10") (pinfunction "10_10") (pintype "bidirectional"))
    )
    (net (code "119") (name "Net-(J2-55)") (class "Default")
      (node (ref "J2") (pin "54") (pinfunction "55_54") (pintype "bidirectional"))
      (node (ref "U$4") (pin "9") (pinfunction "9_9") (pintype "bidirectional"))
    )
    (net (code "120") (name "Net-(J2-56)") (class "Default")
      (node (ref "J2") (pin "55") (pinfunction "56_55") (pintype "bidirectional"))
      (node (ref "U$4") (pin "8") (pinfunction "8_8") (pintype "bidirectional"))
    )
    (net (code "121") (name "Net-(J2-57)") (class "Default")
      (node (ref "J2") (pin "56") (pinfunction "57_56") (pintype "bidirectional"))
      (node (ref "U$4") (pin "7") (pinfunction "7_7") (pintype "bidirectional"))
    )
    (net (code "122") (name "Net-(J2-58)") (class "Default")
      (node (ref "J2") (pin "57") (pinfunction "58_57") (pintype "bidirectional"))
      (node (ref "U$4") (pin "6") (pinfunction "6_6") (pintype "bidirectional"))
    )
    (net (code "123") (name "Net-(J2-59)") (class "Default")
      (node (ref "J2") (pin "58") (pinfunction "59_58") (pintype "bidirectional"))
      (node (ref "U$4") (pin "5") (pinfunction "5_5") (pintype "bidirectional"))
    )
    (net (code "124") (name "Net-(J2-60)") (class "Default")
      (node (ref "J2") (pin "59") (pinfunction "60_59") (pintype "bidirectional"))
      (node (ref "U$4") (pin "4") (pinfunction "4_4") (pintype "bidirectional"))
    )
    (net (code "125") (name "Net-(J2-61)") (class "Default")
      (node (ref "J2") (pin "60") (pinfunction "61_60") (pintype "bidirectional"))
      (node (ref "U$4") (pin "3") (pinfunction "3_3") (pintype "bidirectional"))
    )
    (net (code "126") (name "Net-(J2-62)") (class "Default")
      (node (ref "J2") (pin "61") (pinfunction "62_61") (pintype "bidirectional"))
      (node (ref "U$4") (pin "2") (pinfunction "2_2") (pintype "bidirectional"))
    )
    (net (code "127") (name "Net-(J2-63)") (class "Default")
      (node (ref "J2") (pin "62") (pinfunction "63_62") (pintype "bidirectional"))
      (node (ref "U$4") (pin "1") (pinfunction "1_1") (pintype "bidirectional"))
    )
    (net (code "128") (name "Net-(J2-64)") (class "Default")
      (node (ref "J2") (pin "63") (pinfunction "64_63") (pintype "bidirectional"))
      (node (ref "U$4") (pin "0") (pinfunction "0_0") (pintype "bidirectional"))
    )
    (net (code "129") (name "unconnected-(J1-MNT_1-Pad65)") (class "Default")
      (node (ref "J1") (pin "65") (pinfunction "MNT_1_65") (pintype "bidirectional"))
    )
    (net (code "130") (name "unconnected-(J1-MNT_2-Pad66)") (class "Default")
      (node (ref "J1") (pin "66") (pinfunction "MNT_2_66") (pintype "bidirectional"))
    )
    (net (code "131") (name "unconnected-(J2-MNT_1-Pad65)") (class "Default")
      (node (ref "J2") (pin "65") (pinfunction "MNT_1_65") (pintype "bidirectional"))
    )
    (net (code "132") (name "unconnected-(J2-MNT_2-Pad66)") (class "Default")
      (node (ref "J2") (pin "66") (pinfunction "MNT_2_66") (pintype "bidirectional"))
    )
  )
)
